# I2C-9685-PWM.net
KiCad netlist of a schematic drawn in EAGLE
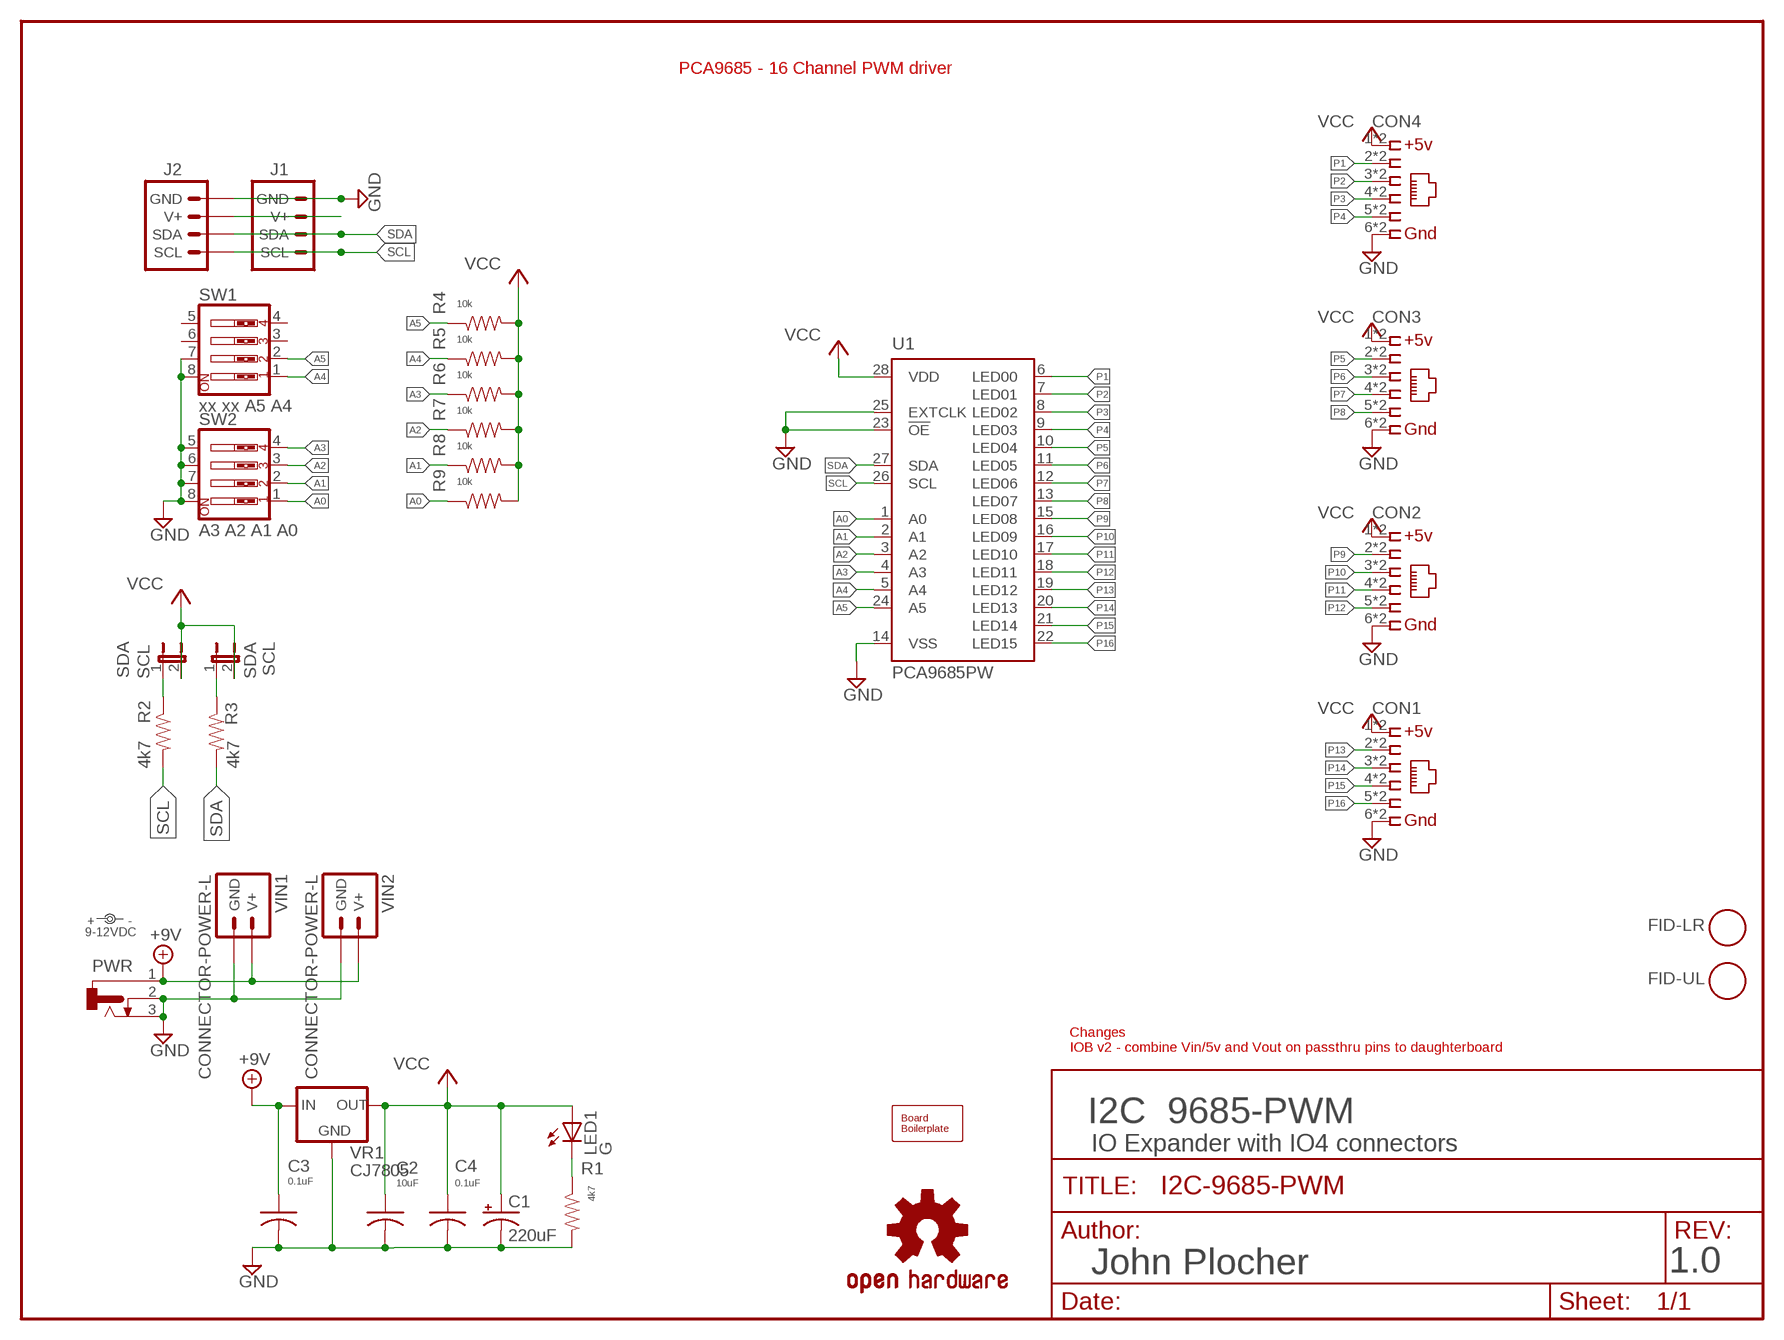
[diagram p0: schematic, sheet 1]

(export (version "E")
  (design (tool "Eeschema 10.0.6"))
  (components
    (comp (ref "BOARD1")
      (value "BOARD80X100-IOB")
      (footprint "eagle-import:BOARD-DINRAIL-3.17IN-IOB")
      (libsource (lib "eagle-import") (part "BOARD80X100-IOB"))
    )
    (comp (ref "C1")
      (value "220uF")
      (footprint "eagle-import:0810-CAP")
      (libsource (lib "eagle-import") (part "CAP-POL0810"))
    )
    (comp (ref "C2")
      (value "10uF")
      (footprint "eagle-import:0805-CAP")
      (libsource (lib "eagle-import") (part "CAP0805"))
    )
    (comp (ref "C3")
      (value "0.1uF")
      (footprint "eagle-import:0805-CAP")
      (libsource (lib "eagle-import") (part "CAP0805"))
    )
    (comp (ref "C4")
      (value "0.1uF")
      (footprint "eagle-import:0805-CAP")
      (libsource (lib "eagle-import") (part "CAP0805"))
    )
    (comp (ref "CON1")
      (value "CONNECTOR-IO4IPINS")
      (footprint "eagle-import:RJ24-INVERTED-PINS")
      (libsource (lib "eagle-import") (part "CONNECTOR-IO4IPINS"))
    )
    (comp (ref "CON2")
      (value "CONNECTOR-IO4IPINS")
      (footprint "eagle-import:RJ24-INVERTED-PINS")
      (libsource (lib "eagle-import") (part "CONNECTOR-IO4IPINS"))
    )
    (comp (ref "CON3")
      (value "CONNECTOR-IO4IPINS")
      (footprint "eagle-import:RJ24-INVERTED-PINS")
      (libsource (lib "eagle-import") (part "CONNECTOR-IO4IPINS"))
    )
    (comp (ref "CON4")
      (value "CONNECTOR-IO4IPINS")
      (footprint "eagle-import:RJ24-INVERTED-PINS")
      (libsource (lib "eagle-import") (part "CONNECTOR-IO4IPINS"))
    )
    (comp (ref "FID-LR")
      (value "FIDUCIAL")
      (footprint "eagle-import:FIDUCIAL_1MM")
      (libsource (lib "eagle-import") (part "FIDUCIAL"))
    )
    (comp (ref "FID-UL")
      (value "FIDUCIAL")
      (footprint "eagle-import:FIDUCIAL_1MM")
      (libsource (lib "eagle-import") (part "FIDUCIAL"))
    )
    (comp (ref "J1")
      (value "CONNECTOR-I2CLEFT")
      (footprint "eagle-import:I2C-L")
      (libsource (lib "eagle-import") (part "CONNECTOR-I2CLEFT"))
    )
    (comp (ref "J2")
      (value "CONNECTOR-I2CLEFT")
      (footprint "eagle-import:I2C-L")
      (libsource (lib "eagle-import") (part "CONNECTOR-I2CLEFT"))
    )
    (comp (ref "LED1")
      (value "G")
      (footprint "eagle-import:0603-LED")
      (libsource (lib "eagle-import") (part "LED0603-LED"))
    )
    (comp (ref "PWR")
      (value "CONNECTOR-DC-POWER-RA")
      (footprint "eagle-import:DCJ0202")
      (libsource (lib "eagle-import") (part "CONNECTOR-DC-POWER-RA"))
    )
    (comp (ref "R1")
      (value "4k7")
      (footprint "eagle-import:0603-RES")
      (libsource (lib "eagle-import") (part "R0603-RES"))
    )
    (comp (ref "R2")
      (value "4k7")
      (footprint "eagle-import:0603-RES")
      (libsource (lib "eagle-import") (part "R0603-RES"))
    )
    (comp (ref "R3")
      (value "4k7")
      (footprint "eagle-import:0603-RES")
      (libsource (lib "eagle-import") (part "R0603-RES"))
    )
    (comp (ref "R4")
      (value "10k")
      (footprint "eagle-import:0603-RES")
      (libsource (lib "eagle-import") (part "R0603-RES"))
    )
    (comp (ref "R5")
      (value "10k")
      (footprint "eagle-import:0603-RES")
      (libsource (lib "eagle-import") (part "R0603-RES"))
    )
    (comp (ref "R6")
      (value "10k")
      (footprint "eagle-import:0603-RES")
      (libsource (lib "eagle-import") (part "R0603-RES"))
    )
    (comp (ref "R7")
      (value "10k")
      (footprint "eagle-import:0603-RES")
      (libsource (lib "eagle-import") (part "R0603-RES"))
    )
    (comp (ref "R8")
      (value "10k")
      (footprint "eagle-import:0603-RES")
      (libsource (lib "eagle-import") (part "R0603-RES"))
    )
    (comp (ref "R9")
      (value "10k")
      (footprint "eagle-import:0603-RES")
      (libsource (lib "eagle-import") (part "R0603-RES"))
    )
    (comp (ref "SCL")
      (value "SDA")
      (footprint "eagle-import:1X02_LOCK")
      (libsource (lib "eagle-import") (part "JUMPER-2PTH_LOCK"))
    )
    (comp (ref "SDA")
      (value "SCL")
      (footprint "eagle-import:1X02_LOCK")
      (libsource (lib "eagle-import") (part "JUMPER-2PTH_LOCK"))
    )
    (comp (ref "SW1")
      (value "xx xx A5 A4")
      (footprint "eagle-import:EDG-04")
      (libsource (lib "eagle-import") (part "SW_DIP-4"))
    )
    (comp (ref "SW2")
      (value "A3 A2 A1 A0")
      (footprint "eagle-import:EDG-04")
      (libsource (lib "eagle-import") (part "SW_DIP-4"))
    )
    (comp (ref "U$1")
      (value "OSHW-LOGOL")
      (footprint "eagle-import:OSHW-LOGO-L")
      (libsource (lib "eagle-import") (part "OSHW-LOGOL"))
    )
    (comp (ref "U1")
      (value "PCA9685PW")
      (footprint "eagle-import:TSSOP28")
      (libsource (lib "eagle-import") (part "PCA9685PW"))
    )
    (comp (ref "VIN")
      (value "9-12VDC")
      (footprint "eagle-import:PWR_LABEL")
      (libsource (lib "eagle-import") (part "DOC-POWER_LABEL"))
    )
    (comp (ref "VIN1")
      (value "CONNECTOR-POWER-L")
      (footprint "eagle-import:POWER-R2")
      (libsource (lib "eagle-import") (part "CONNECTOR-POWER-L"))
    )
    (comp (ref "VIN2")
      (value "CONNECTOR-POWER-L")
      (footprint "eagle-import:POWER-R2")
      (libsource (lib "eagle-import") (part "CONNECTOR-POWER-L"))
    )
    (comp (ref "VR1")
      (value "CJ7805")
      (footprint "eagle-import:TO-252")
      (libsource (lib "eagle-import") (part "VREG-?-DPAK5"))
    )
  )
  (nets
    (net (code "1") (name "+9V") (class "Default")
      (node (ref "C3") (pin "1") (pinfunction "1_1") (pintype "passive"))
      (node (ref "PWR") (pin "1") (pinfunction "1_1") (pintype "passive"))
      (node (ref "VIN1") (pin "V+") (pinfunction "V+_V+") (pintype "passive"))
      (node (ref "VIN1") (pin "V+@1") (pinfunction "V+_V+@1") (pintype "passive"))
      (node (ref "VIN1") (pin "V+@2") (pinfunction "V+_V+@2") (pintype "passive"))
      (node (ref "VIN1") (pin "V+@3") (pinfunction "V+_V+@3") (pintype "passive"))
      (node (ref "VIN2") (pin "V+") (pinfunction "V+_V+") (pintype "passive"))
      (node (ref "VIN2") (pin "V+@1") (pinfunction "V+_V+@1") (pintype "passive"))
      (node (ref "VIN2") (pin "V+@2") (pinfunction "V+_V+@2") (pintype "passive"))
      (node (ref "VIN2") (pin "V+@3") (pinfunction "V+_V+@3") (pintype "passive"))
      (node (ref "VR1") (pin "1") (pinfunction "IN_1") (pintype "input"))
    )
    (net (code "2") (name "A0") (class "Default")
      (node (ref "R9") (pin "1") (pinfunction "1_1") (pintype "passive"))
      (node (ref "SW2") (pin "1") (pinfunction "1_1") (pintype "passive"))
      (node (ref "U1") (pin "1") (pinfunction "A0_1") (pintype "input"))
    )
    (net (code "3") (name "A1") (class "Default")
      (node (ref "R8") (pin "1") (pinfunction "1_1") (pintype "passive"))
      (node (ref "SW2") (pin "2") (pinfunction "2_2") (pintype "passive"))
      (node (ref "U1") (pin "2") (pinfunction "A1_2") (pintype "input"))
    )
    (net (code "4") (name "A2") (class "Default")
      (node (ref "R7") (pin "1") (pinfunction "1_1") (pintype "passive"))
      (node (ref "SW2") (pin "3") (pinfunction "3_3") (pintype "passive"))
      (node (ref "U1") (pin "3") (pinfunction "A2_3") (pintype "input"))
    )
    (net (code "5") (name "A3") (class "Default")
      (node (ref "R6") (pin "1") (pinfunction "1_1") (pintype "passive"))
      (node (ref "SW2") (pin "4") (pinfunction "4_4") (pintype "passive"))
      (node (ref "U1") (pin "4") (pinfunction "A3_4") (pintype "input"))
    )
    (net (code "6") (name "A4") (class "Default")
      (node (ref "R5") (pin "1") (pinfunction "1_1") (pintype "passive"))
      (node (ref "SW1") (pin "1") (pinfunction "1_1") (pintype "passive"))
      (node (ref "U1") (pin "5") (pinfunction "A4_5") (pintype "input"))
    )
    (net (code "7") (name "A5") (class "Default")
      (node (ref "R4") (pin "1") (pinfunction "1_1") (pintype "passive"))
      (node (ref "SW1") (pin "2") (pinfunction "2_2") (pintype "passive"))
      (node (ref "U1") (pin "24") (pinfunction "A5_24") (pintype "input"))
    )
    (net (code "8") (name "GND") (class "Default")
      (node (ref "C1") (pin "-") (pinfunction "-_-") (pintype "passive"))
      (node (ref "C2") (pin "2") (pinfunction "2_2") (pintype "passive"))
      (node (ref "C3") (pin "2") (pinfunction "2_2") (pintype "passive"))
      (node (ref "C4") (pin "2") (pinfunction "2_2") (pintype "passive"))
      (node (ref "CON1") (pin "6") (pinfunction "6_6") (pintype "power_in"))
      (node (ref "CON1") (pin "6@1") (pinfunction "6_6@1") (pintype "power_in"))
      (node (ref "CON2") (pin "6") (pinfunction "6_6") (pintype "power_in"))
      (node (ref "CON2") (pin "6@1") (pinfunction "6_6@1") (pintype "power_in"))
      (node (ref "CON3") (pin "6") (pinfunction "6_6") (pintype "power_in"))
      (node (ref "CON3") (pin "6@1") (pinfunction "6_6@1") (pintype "power_in"))
      (node (ref "CON4") (pin "6") (pinfunction "6_6") (pintype "power_in"))
      (node (ref "CON4") (pin "6@1") (pinfunction "6_6@1") (pintype "power_in"))
      (node (ref "J1") (pin "GND") (pinfunction "GND_GND") (pintype "passive"))
      (node (ref "J1") (pin "GND@1") (pinfunction "GND_GND@1") (pintype "passive"))
      (node (ref "J2") (pin "GND") (pinfunction "GND_GND") (pintype "passive"))
      (node (ref "J2") (pin "GND@1") (pinfunction "GND_GND@1") (pintype "passive"))
      (node (ref "PWR") (pin "2") (pinfunction "2_2") (pintype "passive"))
      (node (ref "PWR") (pin "3") (pinfunction "3_3") (pintype "passive"))
      (node (ref "R1") (pin "2") (pinfunction "2_2") (pintype "passive"))
      (node (ref "SW1") (pin "7") (pinfunction "7_7") (pintype "passive"))
      (node (ref "SW1") (pin "8") (pinfunction "8_8") (pintype "passive"))
      (node (ref "SW2") (pin "5") (pinfunction "5_5") (pintype "passive"))
      (node (ref "SW2") (pin "6") (pinfunction "6_6") (pintype "passive"))
      (node (ref "SW2") (pin "7") (pinfunction "7_7") (pintype "passive"))
      (node (ref "SW2") (pin "8") (pinfunction "8_8") (pintype "passive"))
      (node (ref "U1") (pin "14") (pinfunction "VSS_14") (pintype "power_in"))
      (node (ref "U1") (pin "23") (pinfunction "~{OE}_23") (pintype "input"))
      (node (ref "U1") (pin "25") (pinfunction "EXTCLK_25") (pintype "input"))
      (node (ref "VIN1") (pin "GND") (pinfunction "GND_GND") (pintype "passive"))
      (node (ref "VIN1") (pin "GND@1") (pinfunction "GND_GND@1") (pintype "passive"))
      (node (ref "VIN1") (pin "GND@2") (pinfunction "GND_GND@2") (pintype "passive"))
      (node (ref "VIN1") (pin "GND@3") (pinfunction "GND_GND@3") (pintype "passive"))
      (node (ref "VIN2") (pin "GND") (pinfunction "GND_GND") (pintype "passive"))
      (node (ref "VIN2") (pin "GND@1") (pinfunction "GND_GND@1") (pintype "passive"))
      (node (ref "VIN2") (pin "GND@2") (pinfunction "GND_GND@2") (pintype "passive"))
      (node (ref "VIN2") (pin "GND@3") (pinfunction "GND_GND@3") (pintype "passive"))
      (node (ref "VR1") (pin "2") (pinfunction "GND_2") (pintype "input"))
    )
    (net (code "9") (name "Net-(J1-PadV+)") (class "Default")
      (node (ref "J1") (pin "V+") (pinfunction "V+_V+") (pintype "passive"))
      (node (ref "J1") (pin "V+@1") (pinfunction "V+_V+@1") (pintype "passive"))
      (node (ref "J2") (pin "V+") (pinfunction "V+_V+") (pintype "passive"))
      (node (ref "J2") (pin "V+@1") (pinfunction "V+_V+@1") (pintype "passive"))
    )
    (net (code "10") (name "Net-(LED1-PadC)") (class "Default")
      (node (ref "LED1") (pin "C") (pinfunction "C_C") (pintype "passive"))
      (node (ref "R1") (pin "1") (pinfunction "1_1") (pintype "passive"))
    )
    (net (code "11") (name "Net-(R2-Pad1)") (class "Default")
      (node (ref "R2") (pin "1") (pinfunction "1_1") (pintype "passive"))
      (node (ref "SDA") (pin "1") (pinfunction "1_1") (pintype "passive"))
    )
    (net (code "12") (name "Net-(R3-Pad1)") (class "Default")
      (node (ref "R3") (pin "1") (pinfunction "1_1") (pintype "passive"))
      (node (ref "SCL") (pin "1") (pinfunction "1_1") (pintype "passive"))
    )
    (net (code "13") (name "P1") (class "Default")
      (node (ref "CON4") (pin "2") (pinfunction "2_2") (pintype "passive"))
      (node (ref "CON4") (pin "2@1") (pinfunction "2_2@1") (pintype "passive"))
      (node (ref "U1") (pin "6") (pinfunction "LED00_6") (pintype "output"))
    )
    (net (code "14") (name "P2") (class "Default")
      (node (ref "CON4") (pin "3") (pinfunction "3_3") (pintype "passive"))
      (node (ref "CON4") (pin "3@1") (pinfunction "3_3@1") (pintype "passive"))
      (node (ref "U1") (pin "7") (pinfunction "LED01_7") (pintype "output"))
    )
    (net (code "15") (name "P3") (class "Default")
      (node (ref "CON4") (pin "4") (pinfunction "4_4") (pintype "passive"))
      (node (ref "CON4") (pin "4@1") (pinfunction "4_4@1") (pintype "passive"))
      (node (ref "U1") (pin "8") (pinfunction "LED02_8") (pintype "output"))
    )
    (net (code "16") (name "P4") (class "Default")
      (node (ref "CON4") (pin "5") (pinfunction "5_5") (pintype "passive"))
      (node (ref "CON4") (pin "5@1") (pinfunction "5_5@1") (pintype "passive"))
      (node (ref "U1") (pin "9") (pinfunction "LED03_9") (pintype "output"))
    )
    (net (code "17") (name "P5") (class "Default")
      (node (ref "CON3") (pin "2") (pinfunction "2_2") (pintype "passive"))
      (node (ref "CON3") (pin "2@1") (pinfunction "2_2@1") (pintype "passive"))
      (node (ref "U1") (pin "10") (pinfunction "LED04_10") (pintype "output"))
    )
    (net (code "18") (name "P6") (class "Default")
      (node (ref "CON3") (pin "3") (pinfunction "3_3") (pintype "passive"))
      (node (ref "CON3") (pin "3@1") (pinfunction "3_3@1") (pintype "passive"))
      (node (ref "U1") (pin "11") (pinfunction "LED05_11") (pintype "output"))
    )
    (net (code "19") (name "P7") (class "Default")
      (node (ref "CON3") (pin "4") (pinfunction "4_4") (pintype "passive"))
      (node (ref "CON3") (pin "4@1") (pinfunction "4_4@1") (pintype "passive"))
      (node (ref "U1") (pin "12") (pinfunction "LED06_12") (pintype "output"))
    )
    (net (code "20") (name "P8") (class "Default")
      (node (ref "CON3") (pin "5") (pinfunction "5_5") (pintype "passive"))
      (node (ref "CON3") (pin "5@1") (pinfunction "5_5@1") (pintype "passive"))
      (node (ref "U1") (pin "13") (pinfunction "LED07_13") (pintype "output"))
    )
    (net (code "21") (name "P9") (class "Default")
      (node (ref "CON2") (pin "2") (pinfunction "2_2") (pintype "passive"))
      (node (ref "CON2") (pin "2@1") (pinfunction "2_2@1") (pintype "passive"))
      (node (ref "U1") (pin "15") (pinfunction "LED08_15") (pintype "output"))
    )
    (net (code "22") (name "P10") (class "Default")
      (node (ref "CON2") (pin "3") (pinfunction "3_3") (pintype "passive"))
      (node (ref "CON2") (pin "3@1") (pinfunction "3_3@1") (pintype "passive"))
      (node (ref "U1") (pin "16") (pinfunction "LED09_16") (pintype "output"))
    )
    (net (code "23") (name "P11") (class "Default")
      (node (ref "CON2") (pin "4") (pinfunction "4_4") (pintype "passive"))
      (node (ref "CON2") (pin "4@1") (pinfunction "4_4@1") (pintype "passive"))
      (node (ref "U1") (pin "17") (pinfunction "LED10_17") (pintype "output"))
    )
    (net (code "24") (name "P12") (class "Default")
      (node (ref "CON2") (pin "5") (pinfunction "5_5") (pintype "passive"))
      (node (ref "CON2") (pin "5@1") (pinfunction "5_5@1") (pintype "passive"))
      (node (ref "U1") (pin "18") (pinfunction "LED11_18") (pintype "output"))
    )
    (net (code "25") (name "P13") (class "Default")
      (node (ref "CON1") (pin "2") (pinfunction "2_2") (pintype "passive"))
      (node (ref "CON1") (pin "2@1") (pinfunction "2_2@1") (pintype "passive"))
      (node (ref "U1") (pin "19") (pinfunction "LED12_19") (pintype "output"))
    )
    (net (code "26") (name "P14") (class "Default")
      (node (ref "CON1") (pin "3") (pinfunction "3_3") (pintype "passive"))
      (node (ref "CON1") (pin "3@1") (pinfunction "3_3@1") (pintype "passive"))
      (node (ref "U1") (pin "20") (pinfunction "LED13_20") (pintype "output"))
    )
    (net (code "27") (name "P15") (class "Default")
      (node (ref "CON1") (pin "4") (pinfunction "4_4") (pintype "passive"))
      (node (ref "CON1") (pin "4@1") (pinfunction "4_4@1") (pintype "passive"))
      (node (ref "U1") (pin "21") (pinfunction "LED14_21") (pintype "output"))
    )
    (net (code "28") (name "P16") (class "Default")
      (node (ref "CON1") (pin "5") (pinfunction "5_5") (pintype "passive"))
      (node (ref "CON1") (pin "5@1") (pinfunction "5_5@1") (pintype "passive"))
      (node (ref "U1") (pin "22") (pinfunction "LED15_22") (pintype "output"))
    )
    (net (code "29") (name "SCL") (class "Default")
      (node (ref "J1") (pin "SCL") (pinfunction "SCL_SCL") (pintype "passive"))
      (node (ref "J1") (pin "SCL@1") (pinfunction "SCL_SCL@1") (pintype "passive"))
      (node (ref "J2") (pin "SCL") (pinfunction "SCL_SCL") (pintype "passive"))
      (node (ref "J2") (pin "SCL@1") (pinfunction "SCL_SCL@1") (pintype "passive"))
      (node (ref "R2") (pin "2") (pinfunction "2_2") (pintype "passive"))
      (node (ref "U1") (pin "26") (pinfunction "SCL_26") (pintype "input"))
    )
    (net (code "30") (name "SDA") (class "Default")
      (node (ref "J1") (pin "SDA") (pinfunction "SDA_SDA") (pintype "passive"))
      (node (ref "J1") (pin "SDA@1") (pinfunction "SDA_SDA@1") (pintype "passive"))
      (node (ref "J2") (pin "SDA") (pinfunction "SDA_SDA") (pintype "passive"))
      (node (ref "J2") (pin "SDA@1") (pinfunction "SDA_SDA@1") (pintype "passive"))
      (node (ref "R3") (pin "2") (pinfunction "2_2") (pintype "passive"))
      (node (ref "U1") (pin "27") (pinfunction "SDA_27") (pintype "bidirectional"))
    )
    (net (code "31") (name "VCC") (class "Default")
      (node (ref "C1") (pin "+") (pinfunction "+_+") (pintype "passive"))
      (node (ref "C2") (pin "1") (pinfunction "1_1") (pintype "passive"))
      (node (ref "C4") (pin "1") (pinfunction "1_1") (pintype "passive"))
      (node (ref "CON1") (pin "1") (pinfunction "1_1") (pintype "power_in"))
      (node (ref "CON1") (pin "1@1") (pinfunction "1_1@1") (pintype "power_in"))
      (node (ref "CON2") (pin "1") (pinfunction "1_1") (pintype "power_in"))
      (node (ref "CON2") (pin "1@1") (pinfunction "1_1@1") (pintype "power_in"))
      (node (ref "CON3") (pin "1") (pinfunction "1_1") (pintype "power_in"))
      (node (ref "CON3") (pin "1@1") (pinfunction "1_1@1") (pintype "power_in"))
      (node (ref "CON4") (pin "1") (pinfunction "1_1") (pintype "power_in"))
      (node (ref "CON4") (pin "1@1") (pinfunction "1_1@1") (pintype "power_in"))
      (node (ref "LED1") (pin "A") (pinfunction "A_A") (pintype "passive"))
      (node (ref "R4") (pin "2") (pinfunction "2_2") (pintype "passive"))
      (node (ref "R5") (pin "2") (pinfunction "2_2") (pintype "passive"))
      (node (ref "R6") (pin "2") (pinfunction "2_2") (pintype "passive"))
      (node (ref "R7") (pin "2") (pinfunction "2_2") (pintype "passive"))
      (node (ref "R8") (pin "2") (pinfunction "2_2") (pintype "passive"))
      (node (ref "R9") (pin "2") (pinfunction "2_2") (pintype "passive"))
      (node (ref "SCL") (pin "2") (pinfunction "2_2") (pintype "passive"))
      (node (ref "SDA") (pin "2") (pinfunction "2_2") (pintype "passive"))
      (node (ref "U1") (pin "28") (pinfunction "VDD_28") (pintype "power_in"))
      (node (ref "VR1") (pin "3") (pinfunction "OUT_3") (pintype "output"))
    )
    (net (code "32") (name "unconnected-(SW1-Pad3)") (class "Default")
      (node (ref "SW1") (pin "3") (pinfunction "3_3") (pintype "passive"))
    )
    (net (code "33") (name "unconnected-(SW1-Pad4)") (class "Default")
      (node (ref "SW1") (pin "4") (pinfunction "4_4") (pintype "passive"))
    )
    (net (code "34") (name "unconnected-(SW1-Pad5)") (class "Default")
      (node (ref "SW1") (pin "5") (pinfunction "5_5") (pintype "passive"))
    )
    (net (code "35") (name "unconnected-(SW1-Pad6)") (class "Default")
      (node (ref "SW1") (pin "6") (pinfunction "6_6") (pintype "passive"))
    )
  )
)
